# Canadian_Maid.net
KiCad netlist of a schematic drawn in EAGLE
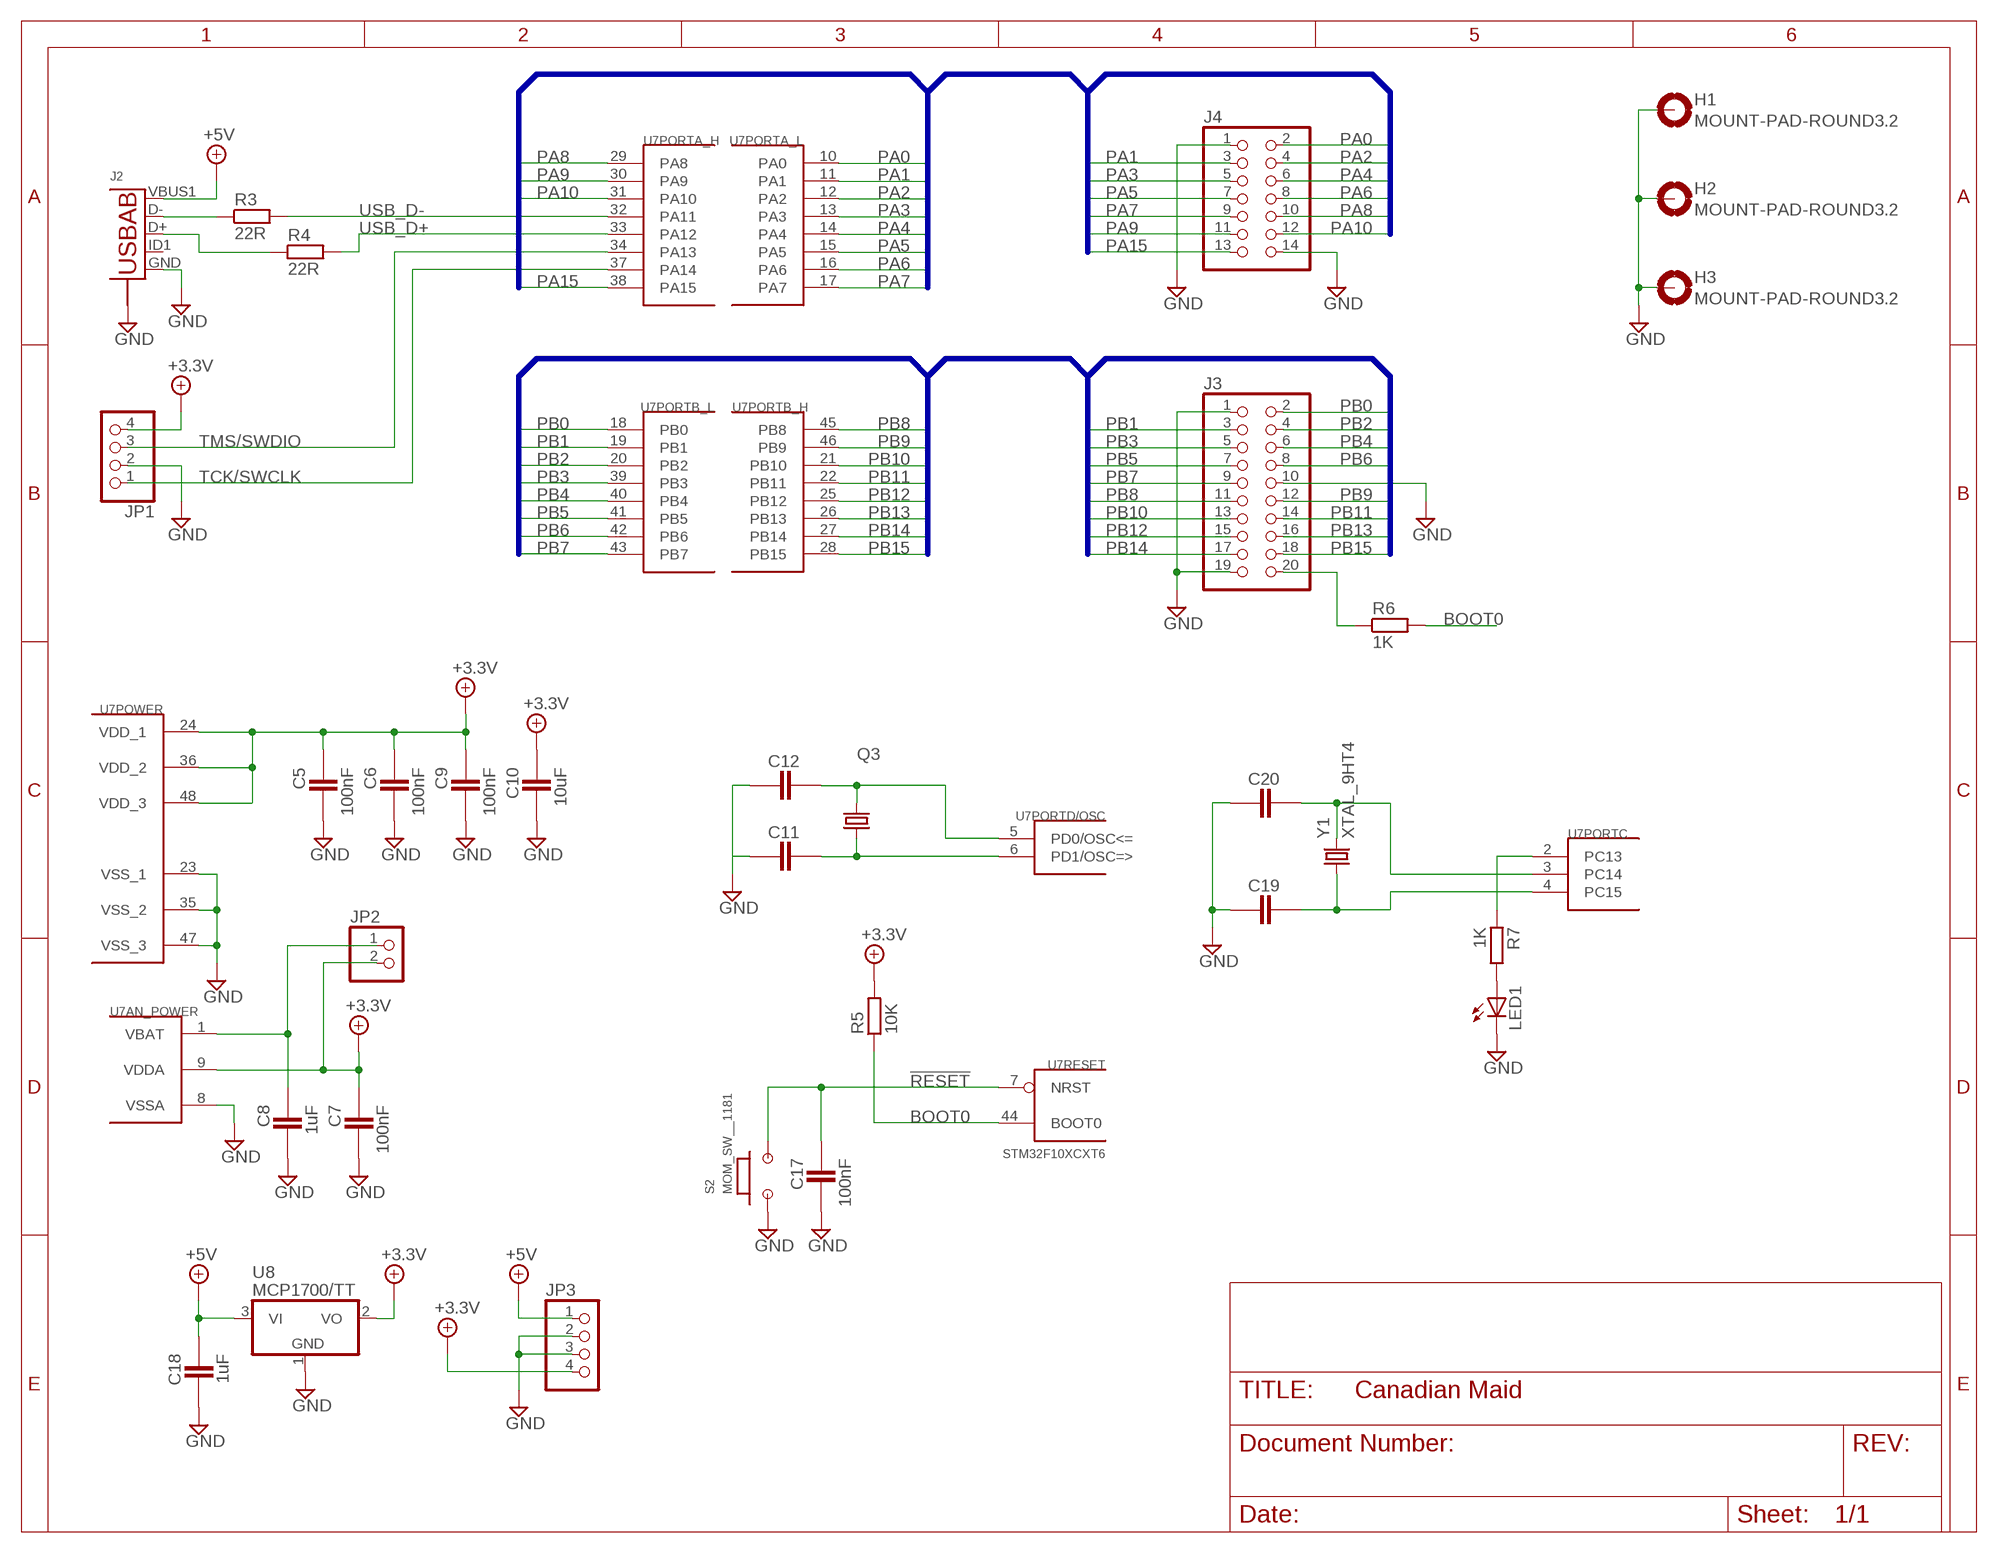
[diagram p0: schematic, sheet 1]

(export (version "E")
  (design (tool "Eeschema 10.0.6"))
  (components
    (comp (ref "C5")
      (value "100nF")
      (footprint "eagle-import:CAPC1005X60N")
      (libsource (lib "eagle-import") (part "CAPACITOR_0402"))
    )
    (comp (ref "C6")
      (value "100nF")
      (footprint "eagle-import:CAPC1005X60N")
      (libsource (lib "eagle-import") (part "CAPACITOR_0402"))
    )
    (comp (ref "C7")
      (value "100nF")
      (footprint "eagle-import:CAPC1005X60N")
      (libsource (lib "eagle-import") (part "CAPACITOR_0402"))
    )
    (comp (ref "C8")
      (value "1uF")
      (footprint "eagle-import:CAPC1005X60N")
      (libsource (lib "eagle-import") (part "CAPACITOR_0402"))
    )
    (comp (ref "C9")
      (value "100nF")
      (footprint "eagle-import:CAPC1005X60N")
      (libsource (lib "eagle-import") (part "CAPACITOR_0402"))
    )
    (comp (ref "C10")
      (value "10uF")
      (footprint "eagle-import:CAPC2012X145AN")
      (libsource (lib "eagle-import") (part "CAPACITOR_0805"))
    )
    (comp (ref "C11")
      (value "CAPACITOR_0402")
      (footprint "eagle-import:CAPC1005X60N")
      (libsource (lib "eagle-import") (part "CAPACITOR_0402"))
    )
    (comp (ref "C12")
      (value "CAPACITOR_0402")
      (footprint "eagle-import:CAPC1005X60N")
      (libsource (lib "eagle-import") (part "CAPACITOR_0402"))
    )
    (comp (ref "C17")
      (value "100nF")
      (footprint "eagle-import:CAPC1005X60N")
      (libsource (lib "eagle-import") (part "CAPACITOR_0402"))
    )
    (comp (ref "C18")
      (value "1uF")
      (footprint "eagle-import:CAPC1608X92N")
      (libsource (lib "eagle-import") (part "CAPACITOR_0603"))
    )
    (comp (ref "C19")
      (value "CAPACITOR_0402")
      (footprint "eagle-import:CAPC1005X60N")
      (libsource (lib "eagle-import") (part "CAPACITOR_0402"))
    )
    (comp (ref "C20")
      (value "CAPACITOR_0402")
      (footprint "eagle-import:CAPC1005X60N")
      (libsource (lib "eagle-import") (part "CAPACITOR_0402"))
    )
    (comp (ref "H1")
      (value "MOUNT-PAD-ROUND3.2")
      (footprint "eagle-import:3,2-PAD")
      (libsource (lib "eagle-import") (part "MOUNT-PAD-ROUND3.2"))
    )
    (comp (ref "H2")
      (value "MOUNT-PAD-ROUND3.2")
      (footprint "eagle-import:3,2-PAD")
      (libsource (lib "eagle-import") (part "MOUNT-PAD-ROUND3.2"))
    )
    (comp (ref "H3")
      (value "MOUNT-PAD-ROUND3.2")
      (footprint "eagle-import:3,2-PAD")
      (libsource (lib "eagle-import") (part "MOUNT-PAD-ROUND3.2"))
    )
    (comp (ref "J2")
      (value "USB-ABBG")
      (footprint "eagle-import:USB-AB-MICRO-SMD_V03_SF")
      (libsource (lib "eagle-import") (part "USB-ABBG"))
    )
    (comp (ref "J3")
      (value "PINHD-2X10_2.54")
      (footprint "eagle-import:2X10")
      (libsource (lib "eagle-import") (part "PINHD-2X10_2.54"))
    )
    (comp (ref "J4")
      (value "PINHD-2X7S")
      (footprint "eagle-import:2X07")
      (libsource (lib "eagle-import") (part "PINHD-2X7S"))
    )
    (comp (ref "JP1")
      (value "PINHD-1X4_2.54")
      (footprint "eagle-import:1X04")
      (libsource (lib "eagle-import") (part "PINHD-1X4_2.54"))
    )
    (comp (ref "JP2")
      (value "PINHD-1X2_2.00")
      (footprint "eagle-import:1X02M")
      (libsource (lib "eagle-import") (part "PINHD-1X2_2.00"))
    )
    (comp (ref "JP3")
      (value "PINHD-1X4_2.54")
      (footprint "eagle-import:1X04")
      (libsource (lib "eagle-import") (part "PINHD-1X4_2.54"))
    )
    (comp (ref "LED1")
      (value "LEDSML0603")
      (footprint "eagle-import:SML0603")
      (libsource (lib "eagle-import") (part "LEDSML0603"))
    )
    (comp (ref "Q3")
      (value "CRYSTALHC49U-V")
      (footprint "eagle-import:HC49U-V")
      (libsource (lib "eagle-import") (part "CRYSTALHC49U-V"))
    )
    (comp (ref "R3")
      (value "22R")
      (footprint "eagle-import:RESC1005X40AN")
      (libsource (lib "eagle-import") (part "RESISTOR_0402"))
    )
    (comp (ref "R4")
      (value "22R")
      (footprint "eagle-import:RESC1005X40AN")
      (libsource (lib "eagle-import") (part "RESISTOR_0402"))
    )
    (comp (ref "R5")
      (value "10K")
      (footprint "eagle-import:RESC1005X40AN")
      (libsource (lib "eagle-import") (part "RESISTOR_0402"))
    )
    (comp (ref "R6")
      (value "1K")
      (footprint "eagle-import:RESC1005X40AN")
      (libsource (lib "eagle-import") (part "RESISTOR_0402"))
    )
    (comp (ref "R7")
      (value "1K")
      (footprint "eagle-import:RESC1005X40AN")
      (libsource (lib "eagle-import") (part "RESISTOR_0402"))
    )
    (comp (ref "S2")
      (value "MOM_SW__1181")
      (footprint "eagle-import:MOM-1181")
      (libsource (lib "eagle-import") (part "MOM_SW__1181"))
    )
    (comp (ref "U7")
      (value "STM32F10XCXT6")
      (footprint "eagle-import:TQFP48")
      (libsource (lib "eagle-import") (part "STM32F10XCXT6"))
    )
    (comp (ref "U8")
      (value "MCP1700/TT")
      (footprint "eagle-import:SOT95P280X135-3N")
      (libsource (lib "eagle-import") (part "MCP1700/TT"))
    )
    (comp (ref "Y1")
      (value "XTAL_9HT4")
      (footprint "eagle-import:9HT7")
      (libsource (lib "eagle-import") (part "XTAL_9HT4"))
    )
  )
  (nets
    (net (code "1") (name "+3.3V") (class "Default")
      (node (ref "C10") (pin "1") (pinfunction "1_1") (pintype "passive"))
      (node (ref "C5") (pin "1") (pinfunction "1_1") (pintype "passive"))
      (node (ref "C6") (pin "1") (pinfunction "1_1") (pintype "passive"))
      (node (ref "C7") (pin "1") (pinfunction "1_1") (pintype "passive"))
      (node (ref "C9") (pin "1") (pinfunction "1_1") (pintype "passive"))
      (node (ref "JP1") (pin "4") (pinfunction "4_4") (pintype "passive"))
      (node (ref "JP2") (pin "2") (pinfunction "2_2") (pintype "passive"))
      (node (ref "JP3") (pin "4") (pinfunction "4_4") (pintype "passive"))
      (node (ref "R5") (pin "2") (pinfunction "2_2") (pintype "passive"))
      (node (ref "U7") (pin "24") (pinfunction "VDD_1_24") (pintype "power_in"))
      (node (ref "U7") (pin "36") (pinfunction "VDD_2_36") (pintype "power_in"))
      (node (ref "U7") (pin "48") (pinfunction "VDD_3_48") (pintype "power_in"))
      (node (ref "U7") (pin "9") (pinfunction "VDDA_9") (pintype "power_in"))
      (node (ref "U8") (pin "2") (pinfunction "VO_2") (pintype "passive"))
    )
    (net (code "2") (name "+5V") (class "Default")
      (node (ref "C18") (pin "1") (pinfunction "1_1") (pintype "passive"))
      (node (ref "J2") (pin "VBUS1") (pinfunction "VBUS_VBUS1") (pintype "bidirectional"))
      (node (ref "JP3") (pin "1") (pinfunction "1_1") (pintype "passive"))
      (node (ref "U8") (pin "3") (pinfunction "VI_3") (pintype "input"))
    )
    (net (code "3") (name "/BOOT0") (class "Default")
      (node (ref "R5") (pin "1") (pinfunction "1_1") (pintype "passive"))
      (node (ref "R6") (pin "2") (pinfunction "2_2") (pintype "passive"))
      (node (ref "U7") (pin "44") (pinfunction "BOOT0_44") (pintype "input"))
    )
    (net (code "4") (name "/PA0") (class "Default")
      (node (ref "J4") (pin "2") (pinfunction "2_2") (pintype "passive"))
      (node (ref "U7") (pin "10") (pinfunction "PA0_10") (pintype "bidirectional"))
    )
    (net (code "5") (name "/PA1") (class "Default")
      (node (ref "J4") (pin "3") (pinfunction "3_3") (pintype "passive"))
      (node (ref "U7") (pin "11") (pinfunction "PA1_11") (pintype "bidirectional"))
    )
    (net (code "6") (name "/PA2") (class "Default")
      (node (ref "J4") (pin "4") (pinfunction "4_4") (pintype "passive"))
      (node (ref "U7") (pin "12") (pinfunction "PA2_12") (pintype "bidirectional"))
    )
    (net (code "7") (name "/PA3") (class "Default")
      (node (ref "J4") (pin "5") (pinfunction "5_5") (pintype "passive"))
      (node (ref "U7") (pin "13") (pinfunction "PA3_13") (pintype "bidirectional"))
    )
    (net (code "8") (name "/PA4") (class "Default")
      (node (ref "J4") (pin "6") (pinfunction "6_6") (pintype "passive"))
      (node (ref "U7") (pin "14") (pinfunction "PA4_14") (pintype "bidirectional"))
    )
    (net (code "9") (name "/PA5") (class "Default")
      (node (ref "J4") (pin "7") (pinfunction "7_7") (pintype "passive"))
      (node (ref "U7") (pin "15") (pinfunction "PA5_15") (pintype "bidirectional"))
    )
    (net (code "10") (name "/PA6") (class "Default")
      (node (ref "J4") (pin "8") (pinfunction "8_8") (pintype "passive"))
      (node (ref "U7") (pin "16") (pinfunction "PA6_16") (pintype "bidirectional"))
    )
    (net (code "11") (name "/PA7") (class "Default")
      (node (ref "J4") (pin "9") (pinfunction "9_9") (pintype "passive"))
      (node (ref "U7") (pin "17") (pinfunction "PA7_17") (pintype "bidirectional"))
    )
    (net (code "12") (name "/PA8") (class "Default")
      (node (ref "J4") (pin "10") (pinfunction "10_10") (pintype "passive"))
      (node (ref "U7") (pin "29") (pinfunction "PA8_29") (pintype "bidirectional"))
    )
    (net (code "13") (name "/PA9") (class "Default")
      (node (ref "J4") (pin "11") (pinfunction "11_11") (pintype "passive"))
      (node (ref "U7") (pin "30") (pinfunction "PA9_30") (pintype "bidirectional"))
    )
    (net (code "14") (name "/PA10") (class "Default")
      (node (ref "J4") (pin "12") (pinfunction "12_12") (pintype "passive"))
      (node (ref "U7") (pin "31") (pinfunction "PA10_31") (pintype "bidirectional"))
    )
    (net (code "15") (name "/PA15") (class "Default")
      (node (ref "J4") (pin "13") (pinfunction "13_13") (pintype "passive"))
      (node (ref "U7") (pin "38") (pinfunction "PA15_38") (pintype "bidirectional"))
    )
    (net (code "16") (name "/PB0") (class "Default")
      (node (ref "J3") (pin "2") (pinfunction "2_2") (pintype "passive"))
      (node (ref "U7") (pin "18") (pinfunction "PB0_18") (pintype "bidirectional"))
    )
    (net (code "17") (name "/PB1") (class "Default")
      (node (ref "J3") (pin "3") (pinfunction "3_3") (pintype "passive"))
      (node (ref "U7") (pin "19") (pinfunction "PB1_19") (pintype "bidirectional"))
    )
    (net (code "18") (name "/PB2") (class "Default")
      (node (ref "J3") (pin "4") (pinfunction "4_4") (pintype "passive"))
      (node (ref "U7") (pin "20") (pinfunction "PB2_20") (pintype "bidirectional"))
    )
    (net (code "19") (name "/PB3") (class "Default")
      (node (ref "J3") (pin "5") (pinfunction "5_5") (pintype "passive"))
      (node (ref "U7") (pin "39") (pinfunction "PB3_39") (pintype "bidirectional"))
    )
    (net (code "20") (name "/PB4") (class "Default")
      (node (ref "J3") (pin "6") (pinfunction "6_6") (pintype "passive"))
      (node (ref "U7") (pin "40") (pinfunction "PB4_40") (pintype "bidirectional"))
    )
    (net (code "21") (name "/PB5") (class "Default")
      (node (ref "J3") (pin "7") (pinfunction "7_7") (pintype "passive"))
      (node (ref "U7") (pin "41") (pinfunction "PB5_41") (pintype "bidirectional"))
    )
    (net (code "22") (name "/PB6") (class "Default")
      (node (ref "J3") (pin "8") (pinfunction "8_8") (pintype "passive"))
      (node (ref "U7") (pin "42") (pinfunction "PB6_42") (pintype "bidirectional"))
    )
    (net (code "23") (name "/PB7") (class "Default")
      (node (ref "J3") (pin "9") (pinfunction "9_9") (pintype "passive"))
      (node (ref "U7") (pin "43") (pinfunction "PB7_43") (pintype "bidirectional"))
    )
    (net (code "24") (name "/PB8") (class "Default")
      (node (ref "J3") (pin "11") (pinfunction "11_11") (pintype "passive"))
      (node (ref "U7") (pin "45") (pinfunction "PB8_45") (pintype "bidirectional"))
    )
    (net (code "25") (name "/PB9") (class "Default")
      (node (ref "J3") (pin "12") (pinfunction "12_12") (pintype "passive"))
      (node (ref "U7") (pin "46") (pinfunction "PB9_46") (pintype "bidirectional"))
    )
    (net (code "26") (name "/PB10") (class "Default")
      (node (ref "J3") (pin "13") (pinfunction "13_13") (pintype "passive"))
      (node (ref "U7") (pin "21") (pinfunction "PB10_21") (pintype "bidirectional"))
    )
    (net (code "27") (name "/PB11") (class "Default")
      (node (ref "J3") (pin "14") (pinfunction "14_14") (pintype "passive"))
      (node (ref "U7") (pin "22") (pinfunction "PB11_22") (pintype "bidirectional"))
    )
    (net (code "28") (name "/PB12") (class "Default")
      (node (ref "J3") (pin "15") (pinfunction "15_15") (pintype "passive"))
      (node (ref "U7") (pin "25") (pinfunction "PB12_25") (pintype "bidirectional"))
    )
    (net (code "29") (name "/PB13") (class "Default")
      (node (ref "J3") (pin "16") (pinfunction "16_16") (pintype "passive"))
      (node (ref "U7") (pin "26") (pinfunction "PB13_26") (pintype "bidirectional"))
    )
    (net (code "30") (name "/PB14") (class "Default")
      (node (ref "J3") (pin "17") (pinfunction "17_17") (pintype "passive"))
      (node (ref "U7") (pin "27") (pinfunction "PB14_27") (pintype "bidirectional"))
    )
    (net (code "31") (name "/PB15") (class "Default")
      (node (ref "J3") (pin "18") (pinfunction "18_18") (pintype "passive"))
      (node (ref "U7") (pin "28") (pinfunction "PB15_28") (pintype "bidirectional"))
    )
    (net (code "32") (name "/TCK{slash}SWCLK") (class "Default")
      (node (ref "JP1") (pin "1") (pinfunction "1_1") (pintype "passive"))
      (node (ref "U7") (pin "37") (pinfunction "PA14_37") (pintype "bidirectional"))
    )
    (net (code "33") (name "/TMS{slash}SWDIO") (class "Default")
      (node (ref "JP1") (pin "3") (pinfunction "3_3") (pintype "passive"))
      (node (ref "U7") (pin "34") (pinfunction "PA13_34") (pintype "bidirectional"))
    )
    (net (code "34") (name "/USB_D+") (class "Default")
      (node (ref "R4") (pin "2") (pinfunction "2_2") (pintype "passive"))
      (node (ref "U7") (pin "33") (pinfunction "PA12_33") (pintype "bidirectional"))
    )
    (net (code "35") (name "/USB_D-") (class "Default")
      (node (ref "R3") (pin "2") (pinfunction "2_2") (pintype "passive"))
      (node (ref "U7") (pin "32") (pinfunction "PA11_32") (pintype "bidirectional"))
    )
    (net (code "36") (name "/~{RESET}") (class "Default")
      (node (ref "C17") (pin "1") (pinfunction "1_1") (pintype "passive"))
      (node (ref "S2") (pin "2") (pinfunction "2_2") (pintype "bidirectional"))
      (node (ref "U7") (pin "7") (pinfunction "NRST_7") (pintype "input"))
    )
    (net (code "37") (name "GND") (class "Default")
      (node (ref "C10") (pin "2") (pinfunction "2_2") (pintype "passive"))
      (node (ref "C11") (pin "1") (pinfunction "1_1") (pintype "passive"))
      (node (ref "C12") (pin "1") (pinfunction "1_1") (pintype "passive"))
      (node (ref "C17") (pin "2") (pinfunction "2_2") (pintype "passive"))
      (node (ref "C18") (pin "2") (pinfunction "2_2") (pintype "passive"))
      (node (ref "C19") (pin "1") (pinfunction "1_1") (pintype "passive"))
      (node (ref "C20") (pin "1") (pinfunction "1_1") (pintype "passive"))
      (node (ref "C5") (pin "2") (pinfunction "2_2") (pintype "passive"))
      (node (ref "C6") (pin "2") (pinfunction "2_2") (pintype "passive"))
      (node (ref "C7") (pin "2") (pinfunction "2_2") (pintype "passive"))
      (node (ref "C8") (pin "2") (pinfunction "2_2") (pintype "passive"))
      (node (ref "C9") (pin "2") (pinfunction "2_2") (pintype "passive"))
      (node (ref "H1") (pin "B3,2") (pinfunction "MOUNT_B3,2") (pintype "passive"))
      (node (ref "H2") (pin "B3,2") (pinfunction "MOUNT_B3,2") (pintype "passive"))
      (node (ref "H3") (pin "B3,2") (pinfunction "MOUNT_B3,2") (pintype "passive"))
      (node (ref "J2") (pin "GND") (pinfunction "GND_GND") (pintype "bidirectional"))
      (node (ref "J2") (pin "S1") (pinfunction "S_S1") (pintype "bidirectional"))
      (node (ref "J2") (pin "S2") (pinfunction "S_S2") (pintype "bidirectional"))
      (node (ref "J2") (pin "S3") (pinfunction "S_S3") (pintype "bidirectional"))
      (node (ref "J2") (pin "S4") (pinfunction "S_S4") (pintype "bidirectional"))
      (node (ref "J3") (pin "1") (pinfunction "1_1") (pintype "passive"))
      (node (ref "J3") (pin "10") (pinfunction "10_10") (pintype "passive"))
      (node (ref "J3") (pin "19") (pinfunction "19_19") (pintype "passive"))
      (node (ref "J4") (pin "1") (pinfunction "1_1") (pintype "passive"))
      (node (ref "J4") (pin "14") (pinfunction "14_14") (pintype "passive"))
      (node (ref "JP1") (pin "2") (pinfunction "2_2") (pintype "passive"))
      (node (ref "JP3") (pin "2") (pinfunction "2_2") (pintype "passive"))
      (node (ref "JP3") (pin "3") (pinfunction "3_3") (pintype "passive"))
      (node (ref "LED1") (pin "C") (pinfunction "C_C") (pintype "passive"))
      (node (ref "S2") (pin "1") (pinfunction "1_1") (pintype "bidirectional"))
      (node (ref "U7") (pin "23") (pinfunction "VSS_1_23") (pintype "power_in"))
      (node (ref "U7") (pin "35") (pinfunction "VSS_2_35") (pintype "power_in"))
      (node (ref "U7") (pin "47") (pinfunction "VSS_3_47") (pintype "power_in"))
      (node (ref "U7") (pin "8") (pinfunction "VSSA_8") (pintype "power_in"))
      (node (ref "U8") (pin "1") (pinfunction "GND_1") (pintype "passive"))
    )
    (net (code "38") (name "Net-(J2-PadD+)") (class "Default")
      (node (ref "J2") (pin "D+") (pinfunction "D+_D+") (pintype "bidirectional"))
      (node (ref "R4") (pin "1") (pinfunction "1_1") (pintype "passive"))
    )
    (net (code "39") (name "Net-(J2-PadD-)") (class "Default")
      (node (ref "J2") (pin "D-") (pinfunction "D-_D-") (pintype "bidirectional"))
      (node (ref "R3") (pin "1") (pinfunction "1_1") (pintype "passive"))
    )
    (net (code "40") (name "Net-(J3-Pad20)") (class "Default")
      (node (ref "J3") (pin "20") (pinfunction "20_20") (pintype "passive"))
      (node (ref "R6") (pin "1") (pinfunction "1_1") (pintype "passive"))
    )
    (net (code "41") (name "Net-(LED1-PadA)") (class "Default")
      (node (ref "LED1") (pin "A") (pinfunction "A_A") (pintype "passive"))
      (node (ref "R7") (pin "2") (pinfunction "2_2") (pintype "passive"))
    )
    (net (code "42") (name "Net-(U7A-VBAT)") (class "Default")
      (node (ref "C8") (pin "1") (pinfunction "1_1") (pintype "passive"))
      (node (ref "JP2") (pin "1") (pinfunction "1_1") (pintype "passive"))
      (node (ref "U7") (pin "1") (pinfunction "VBAT_1") (pintype "power_in"))
    )
    (net (code "43") (name "Net-(U7F-PC13)") (class "Default")
      (node (ref "R7") (pin "1") (pinfunction "1_1") (pintype "passive"))
      (node (ref "U7") (pin "2") (pinfunction "PC13_2") (pintype "bidirectional"))
    )
    (net (code "44") (name "Net-(U7F-PC14)") (class "Default")
      (node (ref "C20") (pin "2") (pinfunction "2_2") (pintype "passive"))
      (node (ref "U7") (pin "3") (pinfunction "PC14_3") (pintype "bidirectional"))
      (node (ref "Y1") (pin "4") (pinfunction "2_4") (pintype "passive"))
    )
    (net (code "45") (name "Net-(U7F-PC15)") (class "Default")
      (node (ref "C19") (pin "2") (pinfunction "2_2") (pintype "passive"))
      (node (ref "U7") (pin "4") (pinfunction "PC15_4") (pintype "bidirectional"))
      (node (ref "Y1") (pin "1") (pinfunction "1_1") (pintype "passive"))
    )
    (net (code "46") (name "Net-(U7G-PD0{slash}OSC<=)") (class "Default")
      (node (ref "C12") (pin "2") (pinfunction "2_2") (pintype "passive"))
      (node (ref "Q3") (pin "2") (pinfunction "2_2") (pintype "passive"))
      (node (ref "U7") (pin "5") (pinfunction "PD0/OSC<=_5") (pintype "bidirectional"))
    )
    (net (code "47") (name "Net-(U7G-PD1{slash}OSC=>)") (class "Default")
      (node (ref "C11") (pin "2") (pinfunction "2_2") (pintype "passive"))
      (node (ref "Q3") (pin "1") (pinfunction "1_1") (pintype "passive"))
      (node (ref "U7") (pin "6") (pinfunction "PD1/OSC=>_6") (pintype "bidirectional"))
    )
    (net (code "48") (name "unconnected-(J2-USBID-PadID1)") (class "Default")
      (node (ref "J2") (pin "ID1") (pinfunction "USBID_ID1") (pintype "bidirectional"))
    )
  )
)
